# 04B-357.net
KiCad netlist of a schematic drawn in EAGLE
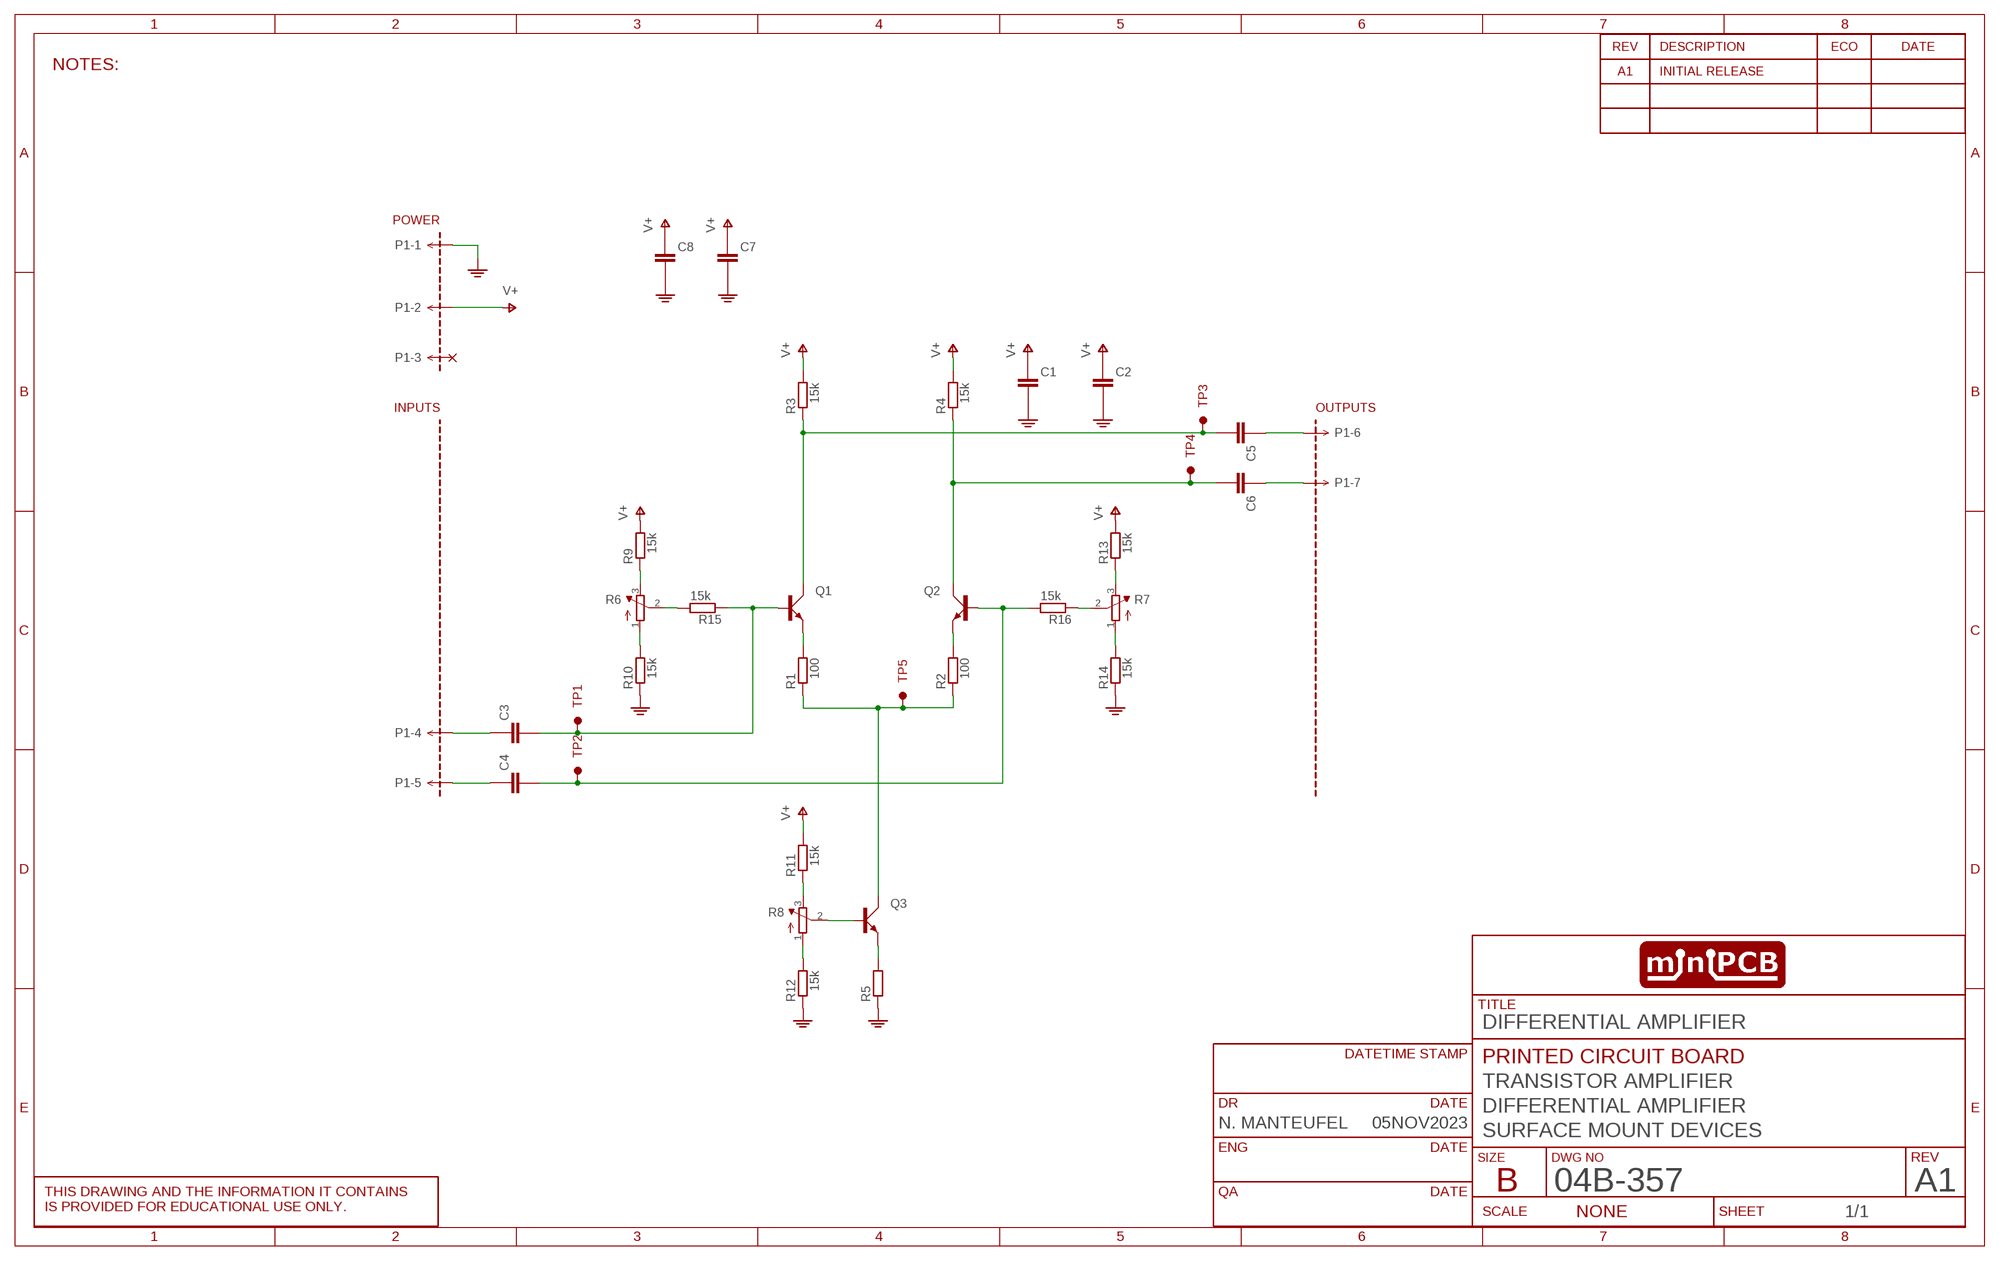
[diagram p0: schematic, sheet 1]

(export (version "E")
  (design (tool "Eeschema 10.0.6"))
  (components
    (comp (ref "C1")
      (value "CAPACITORSMD")
      (footprint "eagle-import:C0805")
      (libsource (lib "eagle-import") (part "CAPACITORSMD"))
    )
    (comp (ref "C2")
      (value "CAPACITORSMD")
      (footprint "eagle-import:C0805")
      (libsource (lib "eagle-import") (part "CAPACITORSMD"))
    )
    (comp (ref "C3")
      (value "CAPACITORSMD")
      (footprint "eagle-import:C0805")
      (libsource (lib "eagle-import") (part "CAPACITORSMD"))
    )
    (comp (ref "C4")
      (value "CAPACITORSMD")
      (footprint "eagle-import:C0805")
      (libsource (lib "eagle-import") (part "CAPACITORSMD"))
    )
    (comp (ref "C5")
      (value "CAPACITORSMD")
      (footprint "eagle-import:C0805")
      (libsource (lib "eagle-import") (part "CAPACITORSMD"))
    )
    (comp (ref "C6")
      (value "CAPACITORSMD")
      (footprint "eagle-import:C0805")
      (libsource (lib "eagle-import") (part "CAPACITORSMD"))
    )
    (comp (ref "C7")
      (value "CAPACITOR1206")
      (footprint "eagle-import:C1206")
      (libsource (lib "eagle-import") (part "CAPACITOR1206"))
    )
    (comp (ref "C8")
      (value "CAPACITOR1206")
      (footprint "eagle-import:C1206")
      (libsource (lib "eagle-import") (part "CAPACITOR1206"))
    )
    (comp (ref "P1")
      (value "MINIPCB_7P")
      (footprint "eagle-import:PINS_1X7")
      (libsource (lib "eagle-import") (part "MINIPCB_7P"))
    )
    (comp (ref "PCB1")
      (value "MINIPCB_0P25X50")
      (footprint "eagle-import:MINIPCB_0P_25X50")
      (fields (field (name "PART_NUMBER") "04B-357") (field (name "TITLE") "DIFFERENTIAL AMPLIFIER"))
      (libsource (lib "eagle-import") (part "MINIPCB_0P25X50"))
    )
    (comp (ref "Q1")
      (value "BJT_NPNBEC")
      (footprint "eagle-import:SOT23")
      (libsource (lib "eagle-import") (part "BJT_NPNBEC"))
    )
    (comp (ref "Q2")
      (value "BJT_NPNBEC")
      (footprint "eagle-import:SOT23")
      (libsource (lib "eagle-import") (part "BJT_NPNBEC"))
    )
    (comp (ref "Q3")
      (value "BJT_NPNBEC")
      (footprint "eagle-import:SOT23")
      (libsource (lib "eagle-import") (part "BJT_NPNBEC"))
    )
    (comp (ref "R1")
      (value "100")
      (footprint "eagle-import:R0805")
      (libsource (lib "eagle-import") (part "RESISTORSMD"))
    )
    (comp (ref "R2")
      (value "100")
      (footprint "eagle-import:R0805")
      (libsource (lib "eagle-import") (part "RESISTORSMD"))
    )
    (comp (ref "R3")
      (value "15k")
      (footprint "eagle-import:R0805")
      (libsource (lib "eagle-import") (part "RESISTORSMD"))
    )
    (comp (ref "R4")
      (value "15k")
      (footprint "eagle-import:R0805")
      (libsource (lib "eagle-import") (part "RESISTORSMD"))
    )
    (comp (ref "R5")
      (value "RESISTORSMD")
      (footprint "eagle-import:R0805")
      (libsource (lib "eagle-import") (part "RESISTORSMD"))
    )
    (comp (ref "R6")
      (value "TRIMPOT0.100THD")
      (footprint "eagle-import:TRIM_0100")
      (libsource (lib "eagle-import") (part "TRIMPOT0.100THD"))
    )
    (comp (ref "R7")
      (value "TRIMPOT0.100THD")
      (footprint "eagle-import:TRIM_0100")
      (libsource (lib "eagle-import") (part "TRIMPOT0.100THD"))
    )
    (comp (ref "R8")
      (value "TRIMPOT0.100THD")
      (footprint "eagle-import:TRIM_0100")
      (libsource (lib "eagle-import") (part "TRIMPOT0.100THD"))
    )
    (comp (ref "R9")
      (value "15k")
      (footprint "eagle-import:R0805")
      (libsource (lib "eagle-import") (part "RESISTORSMD"))
    )
    (comp (ref "R10")
      (value "15k")
      (footprint "eagle-import:R0805")
      (libsource (lib "eagle-import") (part "RESISTORSMD"))
    )
    (comp (ref "R11")
      (value "15k")
      (footprint "eagle-import:R0805")
      (libsource (lib "eagle-import") (part "RESISTORSMD"))
    )
    (comp (ref "R12")
      (value "15k")
      (footprint "eagle-import:R0805")
      (libsource (lib "eagle-import") (part "RESISTORSMD"))
    )
    (comp (ref "R13")
      (value "15k")
      (footprint "eagle-import:R0805")
      (libsource (lib "eagle-import") (part "RESISTORSMD"))
    )
    (comp (ref "R14")
      (value "15k")
      (footprint "eagle-import:R0805")
      (libsource (lib "eagle-import") (part "RESISTORSMD"))
    )
    (comp (ref "R15")
      (value "15k")
      (footprint "eagle-import:R0805")
      (libsource (lib "eagle-import") (part "RESISTORSMD"))
    )
    (comp (ref "R16")
      (value "15k")
      (footprint "eagle-import:R0805")
      (libsource (lib "eagle-import") (part "RESISTORSMD"))
    )
    (comp (ref "TP1")
      (value "TESTPOINTKE5000-SMTEXT")
      (footprint "eagle-import:PINS_1_TESTPOINT_KE5000_NOTEXT")
      (libsource (lib "eagle-import") (part "TESTPOINTKE5000-SMTEXT"))
    )
    (comp (ref "TP2")
      (value "TESTPOINTKE5000-SMTEXT")
      (footprint "eagle-import:PINS_1_TESTPOINT_KE5000_NOTEXT")
      (libsource (lib "eagle-import") (part "TESTPOINTKE5000-SMTEXT"))
    )
    (comp (ref "TP3")
      (value "TESTPOINTKE5000-SMTEXT")
      (footprint "eagle-import:PINS_1_TESTPOINT_KE5000_NOTEXT")
      (libsource (lib "eagle-import") (part "TESTPOINTKE5000-SMTEXT"))
    )
    (comp (ref "TP4")
      (value "TESTPOINTKE5000-SMTEXT")
      (footprint "eagle-import:PINS_1_TESTPOINT_KE5000_NOTEXT")
      (libsource (lib "eagle-import") (part "TESTPOINTKE5000-SMTEXT"))
    )
    (comp (ref "TP5")
      (value "TESTPOINTKE5000-SMTEXT")
      (footprint "eagle-import:PINS_1_TESTPOINT_KE5000_NOTEXT")
      (libsource (lib "eagle-import") (part "TESTPOINTKE5000-SMTEXT"))
    )
  )
  (nets
    (net (code "1") (name "GND") (class "Default")
      (node (ref "C1") (pin "2") (pinfunction "-_2") (pintype "passive"))
      (node (ref "C2") (pin "2") (pinfunction "-_2") (pintype "passive"))
      (node (ref "C7") (pin "-") (pinfunction "-_-") (pintype "passive"))
      (node (ref "C8") (pin "-") (pinfunction "-_-") (pintype "passive"))
      (node (ref "P1") (pin "1") (pinfunction "1_1") (pintype "bidirectional"))
      (node (ref "R10") (pin "1") (pinfunction "1_1") (pintype "passive"))
      (node (ref "R12") (pin "1") (pinfunction "1_1") (pintype "passive"))
      (node (ref "R14") (pin "1") (pinfunction "1_1") (pintype "passive"))
      (node (ref "R5") (pin "1") (pinfunction "1_1") (pintype "passive"))
    )
    (net (code "2") (name "Net-(C3-+)") (class "Default")
      (node (ref "C3") (pin "1") (pinfunction "+_1") (pintype "passive"))
      (node (ref "P1") (pin "4") (pinfunction "1_4") (pintype "bidirectional"))
    )
    (net (code "3") (name "Net-(C3--)") (class "Default")
      (node (ref "C3") (pin "2") (pinfunction "-_2") (pintype "passive"))
      (node (ref "Q1") (pin "1") (pinfunction "B_1") (pintype "passive"))
      (node (ref "R15") (pin "1") (pinfunction "1_1") (pintype "passive"))
      (node (ref "TP1") (pin "1") (pinfunction "1_1") (pintype "bidirectional"))
    )
    (net (code "4") (name "Net-(C4-+)") (class "Default")
      (node (ref "C4") (pin "1") (pinfunction "+_1") (pintype "passive"))
      (node (ref "P1") (pin "5") (pinfunction "1_5") (pintype "bidirectional"))
    )
    (net (code "5") (name "Net-(C4--)") (class "Default")
      (node (ref "C4") (pin "2") (pinfunction "-_2") (pintype "passive"))
      (node (ref "Q2") (pin "1") (pinfunction "B_1") (pintype "passive"))
      (node (ref "R16") (pin "2") (pinfunction "2_2") (pintype "passive"))
      (node (ref "TP2") (pin "1") (pinfunction "1_1") (pintype "bidirectional"))
    )
    (net (code "6") (name "Net-(C5-+)") (class "Default")
      (node (ref "C5") (pin "1") (pinfunction "+_1") (pintype "passive"))
      (node (ref "P1") (pin "6") (pinfunction "1_6") (pintype "bidirectional"))
    )
    (net (code "7") (name "Net-(C5--)") (class "Default")
      (node (ref "C5") (pin "2") (pinfunction "-_2") (pintype "passive"))
      (node (ref "Q1") (pin "3") (pinfunction "C_3") (pintype "passive"))
      (node (ref "R3") (pin "1") (pinfunction "1_1") (pintype "passive"))
      (node (ref "TP3") (pin "1") (pinfunction "1_1") (pintype "bidirectional"))
    )
    (net (code "8") (name "Net-(C6-+)") (class "Default")
      (node (ref "C6") (pin "1") (pinfunction "+_1") (pintype "passive"))
      (node (ref "P1") (pin "7") (pinfunction "1_7") (pintype "bidirectional"))
    )
    (net (code "9") (name "Net-(C6--)") (class "Default")
      (node (ref "C6") (pin "2") (pinfunction "-_2") (pintype "passive"))
      (node (ref "Q2") (pin "3") (pinfunction "C_3") (pintype "passive"))
      (node (ref "R4") (pin "1") (pinfunction "1_1") (pintype "passive"))
      (node (ref "TP4") (pin "1") (pinfunction "1_1") (pintype "bidirectional"))
    )
    (net (code "10") (name "Net-(Q1-E)") (class "Default")
      (node (ref "Q1") (pin "2") (pinfunction "E_2") (pintype "passive"))
      (node (ref "R1") (pin "2") (pinfunction "2_2") (pintype "passive"))
    )
    (net (code "11") (name "Net-(Q2-E)") (class "Default")
      (node (ref "Q2") (pin "2") (pinfunction "E_2") (pintype "passive"))
      (node (ref "R2") (pin "2") (pinfunction "2_2") (pintype "passive"))
    )
    (net (code "12") (name "Net-(Q3-B)") (class "Default")
      (node (ref "Q3") (pin "1") (pinfunction "B_1") (pintype "passive"))
      (node (ref "R8") (pin "2") (pinfunction "S_2") (pintype "passive"))
    )
    (net (code "13") (name "Net-(Q3-C)") (class "Default")
      (node (ref "Q3") (pin "3") (pinfunction "C_3") (pintype "passive"))
      (node (ref "R1") (pin "1") (pinfunction "1_1") (pintype "passive"))
      (node (ref "R2") (pin "1") (pinfunction "1_1") (pintype "passive"))
      (node (ref "TP5") (pin "1") (pinfunction "1_1") (pintype "bidirectional"))
    )
    (net (code "14") (name "Net-(Q3-E)") (class "Default")
      (node (ref "Q3") (pin "2") (pinfunction "E_2") (pintype "passive"))
      (node (ref "R5") (pin "2") (pinfunction "2_2") (pintype "passive"))
    )
    (net (code "15") (name "Net-(R6-A)") (class "Default")
      (node (ref "R10") (pin "2") (pinfunction "2_2") (pintype "passive"))
      (node (ref "R6") (pin "1") (pinfunction "A_1") (pintype "passive"))
    )
    (net (code "16") (name "Net-(R6-E)") (class "Default")
      (node (ref "R6") (pin "3") (pinfunction "E_3") (pintype "passive"))
      (node (ref "R9") (pin "1") (pinfunction "1_1") (pintype "passive"))
    )
    (net (code "17") (name "Net-(R6-S)") (class "Default")
      (node (ref "R15") (pin "2") (pinfunction "2_2") (pintype "passive"))
      (node (ref "R6") (pin "2") (pinfunction "S_2") (pintype "passive"))
    )
    (net (code "18") (name "Net-(R7-A)") (class "Default")
      (node (ref "R14") (pin "2") (pinfunction "2_2") (pintype "passive"))
      (node (ref "R7") (pin "1") (pinfunction "A_1") (pintype "passive"))
    )
    (net (code "19") (name "Net-(R7-E)") (class "Default")
      (node (ref "R13") (pin "1") (pinfunction "1_1") (pintype "passive"))
      (node (ref "R7") (pin "3") (pinfunction "E_3") (pintype "passive"))
    )
    (net (code "20") (name "Net-(R7-S)") (class "Default")
      (node (ref "R16") (pin "1") (pinfunction "1_1") (pintype "passive"))
      (node (ref "R7") (pin "2") (pinfunction "S_2") (pintype "passive"))
    )
    (net (code "21") (name "Net-(R8-A)") (class "Default")
      (node (ref "R12") (pin "2") (pinfunction "2_2") (pintype "passive"))
      (node (ref "R8") (pin "1") (pinfunction "A_1") (pintype "passive"))
    )
    (net (code "22") (name "Net-(R8-E)") (class "Default")
      (node (ref "R11") (pin "1") (pinfunction "1_1") (pintype "passive"))
      (node (ref "R8") (pin "3") (pinfunction "E_3") (pintype "passive"))
    )
    (net (code "23") (name "V+") (class "Default")
      (node (ref "C1") (pin "1") (pinfunction "+_1") (pintype "passive"))
      (node (ref "C2") (pin "1") (pinfunction "+_1") (pintype "passive"))
      (node (ref "C7") (pin "+") (pinfunction "+_+") (pintype "passive"))
      (node (ref "C8") (pin "+") (pinfunction "+_+") (pintype "passive"))
      (node (ref "P1") (pin "2") (pinfunction "1_2") (pintype "bidirectional"))
      (node (ref "R11") (pin "2") (pinfunction "2_2") (pintype "passive"))
      (node (ref "R13") (pin "2") (pinfunction "2_2") (pintype "passive"))
      (node (ref "R3") (pin "2") (pinfunction "2_2") (pintype "passive"))
      (node (ref "R4") (pin "2") (pinfunction "2_2") (pintype "passive"))
      (node (ref "R9") (pin "2") (pinfunction "2_2") (pintype "passive"))
    )
    (net (code "24") (name "unconnected-(P1C-1-Pad3)") (class "Default")
      (node (ref "P1") (pin "3") (pinfunction "1_3") (pintype "bidirectional"))
    )
  )
)
